# PAYL0007_PC_Power.net
KiCad netlist of a schematic drawn in Altium Designer
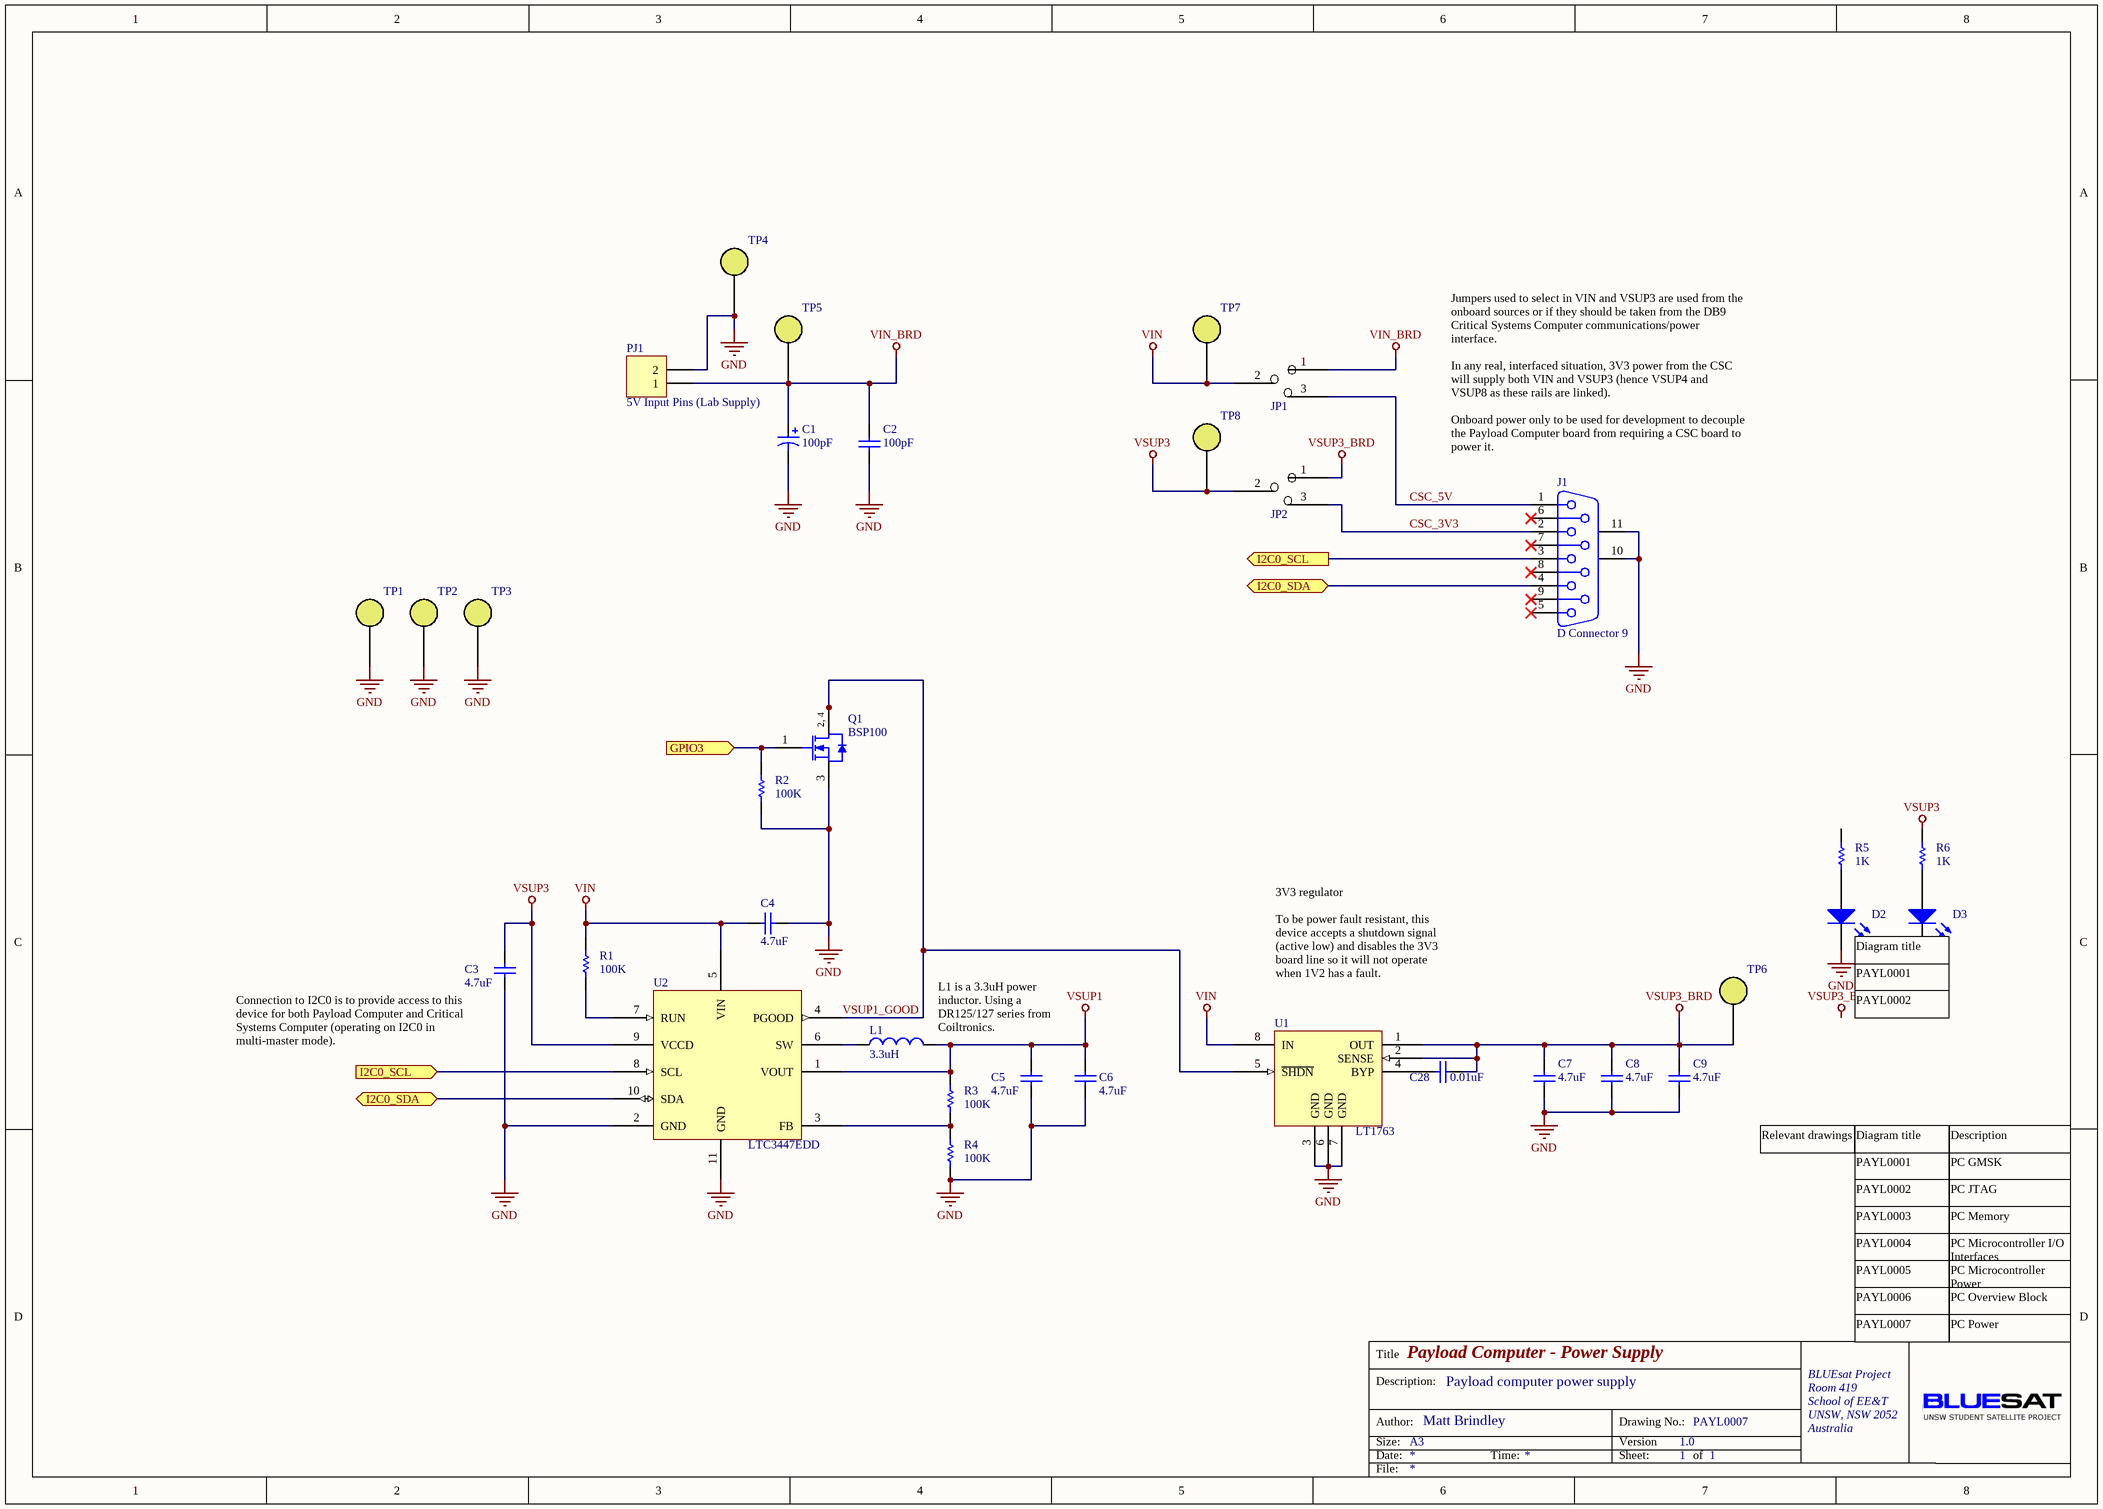
[diagram p0: PAYL0007_PC_Power.SchDoc]

(export (version "E")
  (design (tool "Eeschema 10.0.6"))
  (components
    (comp (ref "C1")
      (value "100pF")
      (footprint "C0805")
      (description "Polarized Capacitor (Surface Mount)")
      (fields (field (name "Comment") "Cap Pol3") (field (name "PUBLISHER") "Altium Limited"))
      (libsource (lib "Miscellaneous Devices") (part "Cap Pol3"))
    )
    (comp (ref "C2")
      (value "100pF")
      (footprint "C0805")
      (description "Capacitor (Semiconductor SIM Model)")
      (fields (field (name "Comment") "Cap Semi") (field (name "PUBLISHER") "Altium Limited"))
      (libsource (lib "Miscellaneous Devices") (part "Cap Semi"))
    )
    (comp (ref "C3")
      (value "4.7uF")
      (footprint "C0805")
      (description "Capacitor (Semiconductor SIM Model)")
      (fields (field (name "Comment") "Cap Semi") (field (name "PUBLISHER") "Altium Limited"))
      (libsource (lib "Miscellaneous Devices") (part "Cap Semi"))
    )
    (comp (ref "C4")
      (value "4.7uF")
      (footprint "C0805")
      (description "Capacitor (Semiconductor SIM Model)")
      (fields (field (name "Comment") "Cap Semi") (field (name "PUBLISHER") "Altium Limited"))
      (libsource (lib "Miscellaneous Devices") (part "Cap Semi"))
    )
    (comp (ref "C5")
      (value "4.7uF")
      (footprint "C0805")
      (description "Capacitor (Semiconductor SIM Model)")
      (fields (field (name "Comment") "Cap Semi") (field (name "PUBLISHER") "Altium Limited"))
      (libsource (lib "Miscellaneous Devices") (part "Cap Semi"))
    )
    (comp (ref "C6")
      (value "4.7uF")
      (footprint "C0805")
      (description "Capacitor (Semiconductor SIM Model)")
      (fields (field (name "Comment") "Cap Semi") (field (name "PUBLISHER") "Altium Limited"))
      (libsource (lib "Miscellaneous Devices") (part "Cap Semi"))
    )
    (comp (ref "C7")
      (value "4.7uF")
      (footprint "C0805")
      (description "Capacitor (Semiconductor SIM Model)")
      (fields (field (name "Comment") "Cap Semi") (field (name "PUBLISHER") "Altium Limited"))
      (libsource (lib "Miscellaneous Devices") (part "Cap Semi"))
    )
    (comp (ref "C8")
      (value "4.7uF")
      (footprint "C0805")
      (description "Capacitor (Semiconductor SIM Model)")
      (fields (field (name "Comment") "Cap Semi") (field (name "PUBLISHER") "Altium Limited"))
      (libsource (lib "Miscellaneous Devices") (part "Cap Semi"))
    )
    (comp (ref "C9")
      (value "4.7uF")
      (footprint "C0805")
      (description "Capacitor (Semiconductor SIM Model)")
      (fields (field (name "Comment") "Cap Semi") (field (name "PUBLISHER") "Altium Limited"))
      (libsource (lib "Miscellaneous Devices") (part "Cap Semi"))
    )
    (comp (ref "C28")
      (value "0.01uF")
      (footprint "C0805")
      (description "Capacitor (Semiconductor SIM Model)")
      (fields (field (name "Comment") "Cap Semi") (field (name "PUBLISHER") "Altium Limited"))
      (libsource (lib "Miscellaneous Devices") (part "Cap Semi"))
    )
    (comp (ref "D2")
      (value "LED2")
      (footprint "DSO-F2/D6.1")
      (description "Typical RED, GREEN, YELLOW, AMBER GaAs LED")
      (fields (field (name "PUBLISHER") "Altium Limited"))
      (libsource (lib "Miscellaneous Devices") (part "LED2"))
    )
    (comp (ref "D3")
      (value "LED2")
      (footprint "DSO-F2/D6.1")
      (description "Typical RED, GREEN, YELLOW, AMBER GaAs LED")
      (fields (field (name "PUBLISHER") "Altium Limited"))
      (libsource (lib "Miscellaneous Devices") (part "LED2"))
    )
    (comp (ref "J1")
      (value "D Connector 9")
      (footprint "DSUB1.385-2H9")
      (description "Receptacle Assembly, 9 Position, Right Angle")
      (fields (field (name "PUBLISHER") "Altium Limited"))
      (libsource (lib "Miscellaneous Connectors") (part "D Connector 9"))
    )
    (comp (ref "JP1")
      (value "Jumper")
      (footprint "HDR1X3")
      (description "3 pin jumper for selection")
      (fields (field (name "PUBLISHER") "Altium Limited"))
      (libsource (lib "PC_Components") (part "2 position jumper"))
    )
    (comp (ref "JP2")
      (value "Jumper")
      (footprint "HDR1X3")
      (description "3 pin jumper for selection")
      (fields (field (name "PUBLISHER") "Altium Limited"))
      (libsource (lib "PC_Components") (part "2 position jumper"))
    )
    (comp (ref "L1")
      (value "3.3uH")
      (footprint "INDC13855X60N")
      (description "Inductor")
      (fields (field (name "PUBLISHER") "Altium Limited"))
      (libsource (lib "Miscellaneous Devices") (part "Inductor"))
    )
    (comp (ref "PJ1")
      (value "5V Input Pins (Lab Supply)")
      (footprint "HDR1X2")
      (description "Header, 2-Pin")
      (fields (field (name "PUBLISHER") "Altium Limited"))
      (libsource (lib "Miscellaneous Connectors") (part "Header 2"))
    )
    (comp (ref "Q1")
      (value "BSP100")
      (footprint "SOT223_N")
      (description "N-channel Enhancement Mode MOSFET")
      (fields (field (name "PUBLISHER") "Altium Limited"))
      (libsource (lib "Philips Discrete MOSFET - Power") (part "BSP100"))
    )
    (comp (ref "R1")
      (value "100K")
      (footprint "6-0805_L")
      (description "Semiconductor Resistor")
      (fields (field (name "Comment") "Res Semi") (field (name "PUBLISHER") "Altium Limited"))
      (libsource (lib "Miscellaneous Devices") (part "Res Semi"))
    )
    (comp (ref "R2")
      (value "100K")
      (footprint "6-0805_L")
      (description "Semiconductor Resistor")
      (fields (field (name "Comment") "Res Semi") (field (name "PUBLISHER") "Altium Limited"))
      (libsource (lib "Miscellaneous Devices") (part "Res Semi"))
    )
    (comp (ref "R3")
      (value "100K")
      (footprint "6-0805_L")
      (description "Semiconductor Resistor")
      (fields (field (name "Comment") "Res Semi") (field (name "PUBLISHER") "Altium Limited"))
      (libsource (lib "Miscellaneous Devices") (part "Res Semi"))
    )
    (comp (ref "R4")
      (value "100K")
      (footprint "6-0805_L")
      (description "Semiconductor Resistor")
      (fields (field (name "Comment") "Res Semi") (field (name "PUBLISHER") "Altium Limited"))
      (libsource (lib "Miscellaneous Devices") (part "Res Semi"))
    )
    (comp (ref "R5")
      (value "1K")
      (footprint "6-0805_L")
      (description "Semiconductor Resistor")
      (fields (field (name "Comment") "Res Semi") (field (name "PUBLISHER") "Altium Limited"))
      (libsource (lib "Miscellaneous Devices") (part "Res Semi"))
    )
    (comp (ref "R6")
      (value "1K")
      (footprint "6-0805_L")
      (description "Semiconductor Resistor")
      (fields (field (name "Comment") "Res Semi") (field (name "PUBLISHER") "Altium Limited"))
      (libsource (lib "Miscellaneous Devices") (part "Res Semi"))
    )
    (comp (ref "TP1")
      (value "Test Point")
      (footprint "PIN1")
      (description "Test point")
      (fields (field (name "PUBLISHER") "Altium Limited"))
      (libsource (lib "PC_Components") (part "Test Point"))
    )
    (comp (ref "TP2")
      (value "Test Point")
      (footprint "PIN1")
      (description "Test point")
      (fields (field (name "PUBLISHER") "Altium Limited"))
      (libsource (lib "PC_Components") (part "Test Point"))
    )
    (comp (ref "TP3")
      (value "Test Point")
      (footprint "PIN1")
      (description "Test point")
      (fields (field (name "PUBLISHER") "Altium Limited"))
      (libsource (lib "PC_Components") (part "Test Point"))
    )
    (comp (ref "TP4")
      (value "Test Point")
      (footprint "PIN1")
      (description "Test point")
      (fields (field (name "PUBLISHER") "Altium Limited"))
      (libsource (lib "PC_Components") (part "Test Point"))
    )
    (comp (ref "TP5")
      (value "Test Point")
      (footprint "PIN1")
      (description "Test point")
      (fields (field (name "PUBLISHER") "Altium Limited"))
      (libsource (lib "PC_Components") (part "Test Point"))
    )
    (comp (ref "TP6")
      (value "Test Point")
      (footprint "PIN1")
      (description "Test point")
      (fields (field (name "PUBLISHER") "Altium Limited"))
      (libsource (lib "PC_Components") (part "Test Point"))
    )
    (comp (ref "TP7")
      (value "Test Point")
      (footprint "PIN1")
      (description "Test point")
      (fields (field (name "PUBLISHER") "Altium Limited"))
      (libsource (lib "PC_Components") (part "Test Point"))
    )
    (comp (ref "TP8")
      (value "Test Point")
      (footprint "PIN1")
      (description "Test point")
      (fields (field (name "PUBLISHER") "Altium Limited"))
      (libsource (lib "PC_Components") (part "Test Point"))
    )
    (comp (ref "U1")
      (value "LT1763")
      (footprint "SOIC127P600X175-8N")
      (description "Linear Technology Voltage Regulator")
      (fields (field (name "PUBLISHER") "Altium Limited"))
      (libsource (lib "PC_Components") (part "LT1763"))
    )
    (comp (ref "U2")
      (value "LTC3447EDD")
      (footprint "LTC3447_DFP11")
      (description "I2C Controlled VReg")
      (fields (field (name "PUBLISHER") "Altium Limited"))
      (libsource (lib "PC_Components") (part "LTC3447EDD"))
    )
  )
  (nets
    (net (code "1") (name "/CSC_3V3") (class "Default")
      (node (ref "J1") (pin "2") (pinfunction "2_2") (pintype "passive"))
      (node (ref "JP2") (pin "3") (pinfunction "3_3") (pintype "passive"))
    )
    (net (code "2") (name "/CSC_5V") (class "Default")
      (node (ref "J1") (pin "1") (pinfunction "1_1") (pintype "passive"))
      (node (ref "JP1") (pin "3") (pinfunction "3_3") (pintype "passive"))
    )
    (net (code "3") (name "/GPIO3") (class "Default")
      (node (ref "Q1") (pin "1") (pinfunction "G_1") (pintype "passive"))
      (node (ref "R2") (pin "2") (pinfunction "2_2") (pintype "passive"))
    )
    (net (code "4") (name "/I2C0_SCL") (class "Default")
      (node (ref "J1") (pin "3") (pinfunction "3_3") (pintype "passive"))
      (node (ref "U2") (pin "8") (pinfunction "SCL_8") (pintype "input"))
    )
    (net (code "5") (name "/I2C0_SDA") (class "Default")
      (node (ref "J1") (pin "4") (pinfunction "4_4") (pintype "passive"))
      (node (ref "U2") (pin "10") (pinfunction "SDA_10") (pintype "bidirectional"))
    )
    (net (code "6") (name "/VSUP1_GOOD") (class "Default")
      (node (ref "Q1") (pin "2") (pinfunction "D_2") (pintype "passive"))
      (node (ref "Q1") (pin "4") (pinfunction "D_4") (pintype "passive"))
      (node (ref "U1") (pin "5") (pinfunction "~{SHDN}_5") (pintype "input"))
      (node (ref "U2") (pin "4") (pinfunction "PGOOD_4") (pintype "output"))
    )
    (net (code "7") (name "GND") (class "Default")
      (node (ref "C1") (pin "2") (pinfunction "2_2") (pintype "passive"))
      (node (ref "C2") (pin "1") (pinfunction "1_1") (pintype "passive"))
      (node (ref "C3") (pin "2") (pinfunction "2_2") (pintype "passive"))
      (node (ref "C4") (pin "1") (pinfunction "1_1") (pintype "passive"))
      (node (ref "C5") (pin "2") (pinfunction "2_2") (pintype "passive"))
      (node (ref "C6") (pin "2") (pinfunction "2_2") (pintype "passive"))
      (node (ref "C7") (pin "2") (pinfunction "2_2") (pintype "passive"))
      (node (ref "C8") (pin "2") (pinfunction "2_2") (pintype "passive"))
      (node (ref "C9") (pin "2") (pinfunction "2_2") (pintype "passive"))
      (node (ref "D2") (pin "2") (pinfunction "K_2") (pintype "passive"))
      (node (ref "D3") (pin "2") (pinfunction "K_2") (pintype "passive"))
      (node (ref "J1") (pin "10") (pinfunction "MH1_10") (pintype "passive"))
      (node (ref "J1") (pin "11") (pinfunction "MH2_11") (pintype "passive"))
      (node (ref "PJ1") (pin "2") (pinfunction "2_2") (pintype "passive"))
      (node (ref "Q1") (pin "3") (pinfunction "S_3") (pintype "passive"))
      (node (ref "R2") (pin "1") (pinfunction "1_1") (pintype "passive"))
      (node (ref "R4") (pin "1") (pinfunction "1_1") (pintype "passive"))
      (node (ref "TP1") (pin "1") (pinfunction "1_1") (pintype "passive"))
      (node (ref "TP2") (pin "1") (pinfunction "1_1") (pintype "passive"))
      (node (ref "TP3") (pin "1") (pinfunction "1_1") (pintype "passive"))
      (node (ref "TP4") (pin "1") (pinfunction "1_1") (pintype "passive"))
      (node (ref "U1") (pin "3") (pinfunction "GND_3") (pintype "power_in"))
      (node (ref "U1") (pin "6") (pinfunction "GND_6") (pintype "power_in"))
      (node (ref "U1") (pin "7") (pinfunction "GND_7") (pintype "power_in"))
      (node (ref "U2") (pin "11") (pinfunction "GND_11") (pintype "power_in"))
      (node (ref "U2") (pin "2") (pinfunction "GND_2") (pintype "power_in"))
    )
    (net (code "8") (name "Net-(D2-A)") (class "Default")
      (node (ref "D2") (pin "1") (pinfunction "A_1") (pintype "passive"))
      (node (ref "R5") (pin "1") (pinfunction "1_1") (pintype "passive"))
    )
    (net (code "9") (name "Net-(D3-A)") (class "Default")
      (node (ref "D3") (pin "1") (pinfunction "A_1") (pintype "passive"))
      (node (ref "R6") (pin "1") (pinfunction "1_1") (pintype "passive"))
    )
    (net (code "10") (name "Net-(U1-BYP)") (class "Default")
      (node (ref "C28") (pin "1") (pinfunction "1_1") (pintype "passive"))
      (node (ref "U1") (pin "4") (pinfunction "BYP_4") (pintype "passive"))
    )
    (net (code "11") (name "Net-(U2-FB)") (class "Default")
      (node (ref "R3") (pin "1") (pinfunction "1_1") (pintype "passive"))
      (node (ref "R4") (pin "2") (pinfunction "2_2") (pintype "passive"))
      (node (ref "U2") (pin "3") (pinfunction "FB_3") (pintype "open_collector"))
    )
    (net (code "12") (name "Net-(U2-RUN)") (class "Default")
      (node (ref "R1") (pin "1") (pinfunction "1_1") (pintype "passive"))
      (node (ref "U2") (pin "7") (pinfunction "RUN_7") (pintype "input"))
    )
    (net (code "13") (name "Net-(U2-SW)") (class "Default")
      (node (ref "L1") (pin "1") (pinfunction "1_1") (pintype "passive"))
      (node (ref "U2") (pin "6") (pinfunction "SW_6") (pintype "open_emitter"))
    )
    (net (code "14") (name "VIN") (class "Default")
      (node (ref "C4") (pin "2") (pinfunction "2_2") (pintype "passive"))
      (node (ref "JP1") (pin "2") (pinfunction "2_2") (pintype "passive"))
      (node (ref "R1") (pin "2") (pinfunction "2_2") (pintype "passive"))
      (node (ref "TP7") (pin "1") (pinfunction "1_1") (pintype "passive"))
      (node (ref "U1") (pin "8") (pinfunction "IN_8") (pintype "power_in"))
      (node (ref "U2") (pin "5") (pinfunction "VIN_5") (pintype "power_in"))
    )
    (net (code "15") (name "VIN_BRD") (class "Default")
      (node (ref "C1") (pin "1") (pinfunction "1_1") (pintype "passive"))
      (node (ref "C2") (pin "2") (pinfunction "2_2") (pintype "passive"))
      (node (ref "JP1") (pin "1") (pinfunction "1_1") (pintype "passive"))
      (node (ref "PJ1") (pin "1") (pinfunction "1_1") (pintype "passive"))
      (node (ref "TP5") (pin "1") (pinfunction "1_1") (pintype "passive"))
    )
    (net (code "16") (name "VSUP1") (class "Default")
      (node (ref "C5") (pin "1") (pinfunction "1_1") (pintype "passive"))
      (node (ref "C6") (pin "1") (pinfunction "1_1") (pintype "passive"))
      (node (ref "L1") (pin "2") (pinfunction "2_2") (pintype "passive"))
      (node (ref "R3") (pin "2") (pinfunction "2_2") (pintype "passive"))
      (node (ref "U2") (pin "1") (pinfunction "VOUT_1") (pintype "power_in"))
    )
    (net (code "17") (name "VSUP3") (class "Default")
      (node (ref "C3") (pin "1") (pinfunction "1_1") (pintype "passive"))
      (node (ref "JP2") (pin "2") (pinfunction "2_2") (pintype "passive"))
      (node (ref "R6") (pin "2") (pinfunction "2_2") (pintype "passive"))
      (node (ref "TP8") (pin "1") (pinfunction "1_1") (pintype "passive"))
      (node (ref "U2") (pin "9") (pinfunction "VCCD_9") (pintype "power_in"))
    )
    (net (code "18") (name "VSUP3_BRD") (class "Default")
      (node (ref "C28") (pin "2") (pinfunction "2_2") (pintype "passive"))
      (node (ref "C7") (pin "1") (pinfunction "1_1") (pintype "passive"))
      (node (ref "C8") (pin "1") (pinfunction "1_1") (pintype "passive"))
      (node (ref "C9") (pin "1") (pinfunction "1_1") (pintype "passive"))
      (node (ref "JP2") (pin "1") (pinfunction "1_1") (pintype "passive"))
      (node (ref "TP6") (pin "1") (pinfunction "1_1") (pintype "passive"))
      (node (ref "U1") (pin "1") (pinfunction "OUT_1") (pintype "power_in"))
      (node (ref "U1") (pin "2") (pinfunction "SENSE_2") (pintype "input"))
    )
    (net (code "19") (name "unconnected-(J1-Pad5)") (class "Default")
      (node (ref "J1") (pin "5") (pinfunction "5_5") (pintype "passive+no_connect"))
    )
    (net (code "20") (name "unconnected-(J1-Pad6)") (class "Default")
      (node (ref "J1") (pin "6") (pinfunction "6_6") (pintype "passive+no_connect"))
    )
    (net (code "21") (name "unconnected-(J1-Pad7)") (class "Default")
      (node (ref "J1") (pin "7") (pinfunction "7_7") (pintype "passive+no_connect"))
    )
    (net (code "22") (name "unconnected-(J1-Pad8)") (class "Default")
      (node (ref "J1") (pin "8") (pinfunction "8_8") (pintype "passive+no_connect"))
    )
    (net (code "23") (name "unconnected-(J1-Pad9)") (class "Default")
      (node (ref "J1") (pin "9") (pinfunction "9_9") (pintype "passive+no_connect"))
    )
    (net (code "24") (name "unconnected-(R5-Pad2)") (class "Default")
      (node (ref "R5") (pin "2") (pinfunction "2_2") (pintype "passive"))
    )
  )
)
